# atarimovie.net
KiCad netlist of a schematic drawn in EAGLE
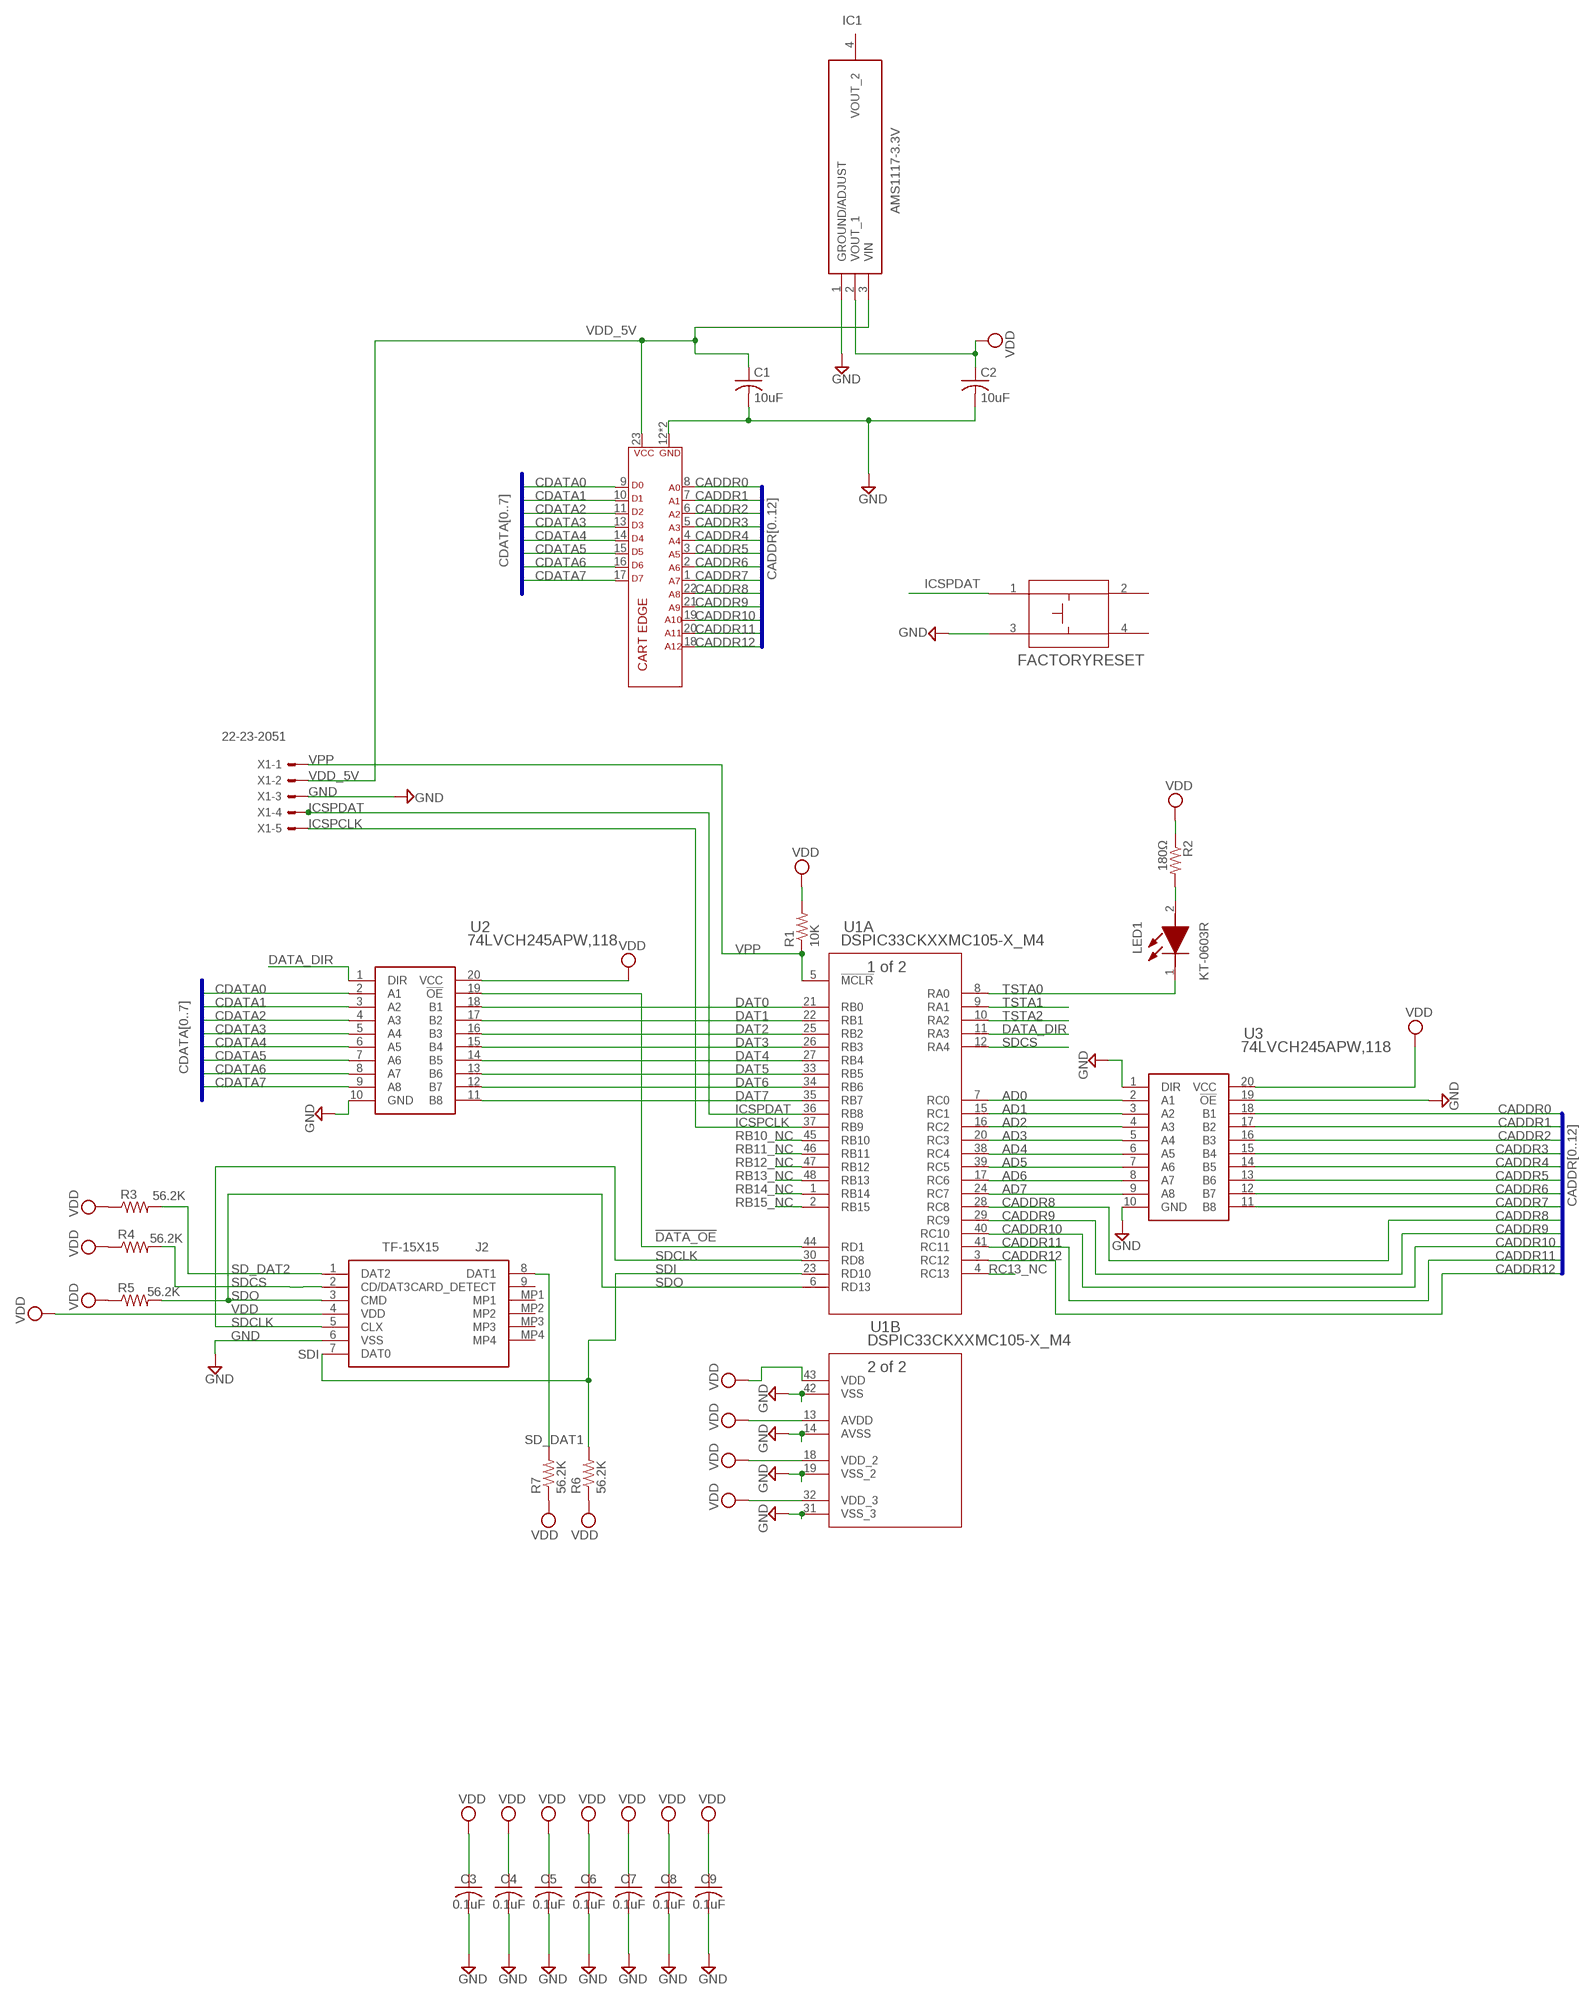
[diagram p0: schematic, sheet 1]

(export (version "E")
  (design (tool "Eeschema 10.0.6"))
  (components
    (comp (ref "C1")
      (value "10uF")
      (footprint "eagle-import:C0603K")
      (libsource (lib "eagle-import") (part "C-USC0603K"))
    )
    (comp (ref "C2")
      (value "10uF")
      (footprint "eagle-import:C0603K")
      (libsource (lib "eagle-import") (part "C-USC0603K"))
    )
    (comp (ref "C3")
      (value "0.1uF")
      (footprint "eagle-import:C0603K")
      (libsource (lib "eagle-import") (part "C-USC0603K"))
    )
    (comp (ref "C4")
      (value "0.1uF")
      (footprint "eagle-import:C0603K")
      (libsource (lib "eagle-import") (part "C-USC0603K"))
    )
    (comp (ref "C5")
      (value "0.1uF")
      (footprint "eagle-import:C0603K")
      (libsource (lib "eagle-import") (part "C-USC0603K"))
    )
    (comp (ref "C6")
      (value "0.1uF")
      (footprint "eagle-import:C0603K")
      (libsource (lib "eagle-import") (part "C-USC0603K"))
    )
    (comp (ref "C7")
      (value "0.1uF")
      (footprint "eagle-import:C0603K")
      (libsource (lib "eagle-import") (part "C-USC0603K"))
    )
    (comp (ref "C8")
      (value "0.1uF")
      (footprint "eagle-import:C0603K")
      (libsource (lib "eagle-import") (part "C-USC0603K"))
    )
    (comp (ref "C9")
      (value "0.1uF")
      (footprint "eagle-import:C0603K")
      (libsource (lib "eagle-import") (part "C-USC0603K"))
    )
    (comp (ref "FACTORYRESET")
      (value "RT3301AF260Q")
      (footprint "eagle-import:RT3301_EWI")
      (fields (field (name "COPYRIGHT") "Copyright (C) 2025 Ultra Librarian. All rights reserved."))
      (libsource (lib "eagle-import") (part "RT3301AF260Q"))
    )
    (comp (ref "IC1")
      (value "AMS1117-3.3V")
      (footprint "eagle-import:SOT229P700X180-4N")
      (fields (field (name "MANUFACTURER_PART_NUMBER") "ams1117-3.3v"))
      (libsource (lib "eagle-import") (part "AMS1117-3.3V"))
    )
    (comp (ref "J1")
      (value "CARTRIDGE EDGE")
      (footprint "eagle-import:MED_TABS_SDACCESS")
      (libsource (lib "eagle-import") (part "ATARI-2600MED_TABS_SDACCESS"))
    )
    (comp (ref "J2")
      (value "TF-15X15")
      (footprint "eagle-import:TF15X15")
      (libsource (lib "eagle-import") (part "TF-15X15"))
    )
    (comp (ref "LED1")
      (value "KT-0603R")
      (footprint "eagle-import:LEDC1608X70N")
      (libsource (lib "eagle-import") (part "KT-0603R"))
    )
    (comp (ref "R1")
      (value "10K")
      (footprint "eagle-import:R0603")
      (libsource (lib "eagle-import") (part "R-US_R0603"))
    )
    (comp (ref "R2")
      (value "180Ω")
      (footprint "eagle-import:R0603")
      (libsource (lib "eagle-import") (part "R-US_R0603"))
    )
    (comp (ref "R3")
      (value "56.2K")
      (footprint "eagle-import:R0603")
      (libsource (lib "eagle-import") (part "R-US_R0603"))
    )
    (comp (ref "R4")
      (value "56.2K")
      (footprint "eagle-import:R0603")
      (libsource (lib "eagle-import") (part "R-US_R0603"))
    )
    (comp (ref "R5")
      (value "56.2K")
      (footprint "eagle-import:R0603")
      (libsource (lib "eagle-import") (part "R-US_R0603"))
    )
    (comp (ref "R6")
      (value "56.2K")
      (footprint "eagle-import:R0603")
      (libsource (lib "eagle-import") (part "R-US_R0603"))
    )
    (comp (ref "R7")
      (value "56.2K")
      (footprint "eagle-import:R0603")
      (libsource (lib "eagle-import") (part "R-US_R0603"))
    )
    (comp (ref "U1")
      (value "DSPIC33CKXXMC105-X_M4")
      (footprint "eagle-import:UQFN48_6X6MC_MCH")
      (fields
        (field (name "MANUFACTURER_PART_NUMBER") "dsPIC33CKXXMC105-X_M4")
        (field (name "COPYRIGHT") "Copyright (C) 2022 Ultra Librarian. All rights reserved.")
      )
      (libsource (lib "eagle-import") (part "DSPIC33CKXXMC105-X_M4"))
    )
    (comp (ref "U2")
      (value "74LVCH245APW,118")
      (footprint "eagle-import:SOP65P640X110-20N")
      (fields (field (name "MOUSER_PART_NUMBER") "771-74LVCH245APW-T"))
      (libsource (lib "eagle-import") (part "74LVCH245APW,118"))
    )
    (comp (ref "U3")
      (value "74LVCH245APW,118")
      (footprint "eagle-import:SOP65P640X110-20N")
      (fields (field (name "MOUSER_PART_NUMBER") "771-74LVCH245APW-T"))
      (libsource (lib "eagle-import") (part "74LVCH245APW,118"))
    )
    (comp (ref "X1")
      (value "22-23-2051")
      (footprint "eagle-import:22-23-2051")
      (fields (field (name "MF") "MOLEX"))
      (libsource (lib "eagle-import") (part "22-23-2051"))
    )
  )
  (nets
    (net (code "1") (name "/AD0") (class "Default")
      (node (ref "U1") (pin "7") (pinfunction "RC0_7") (pintype "bidirectional"))
      (node (ref "U3") (pin "2") (pinfunction "A1_2") (pintype "bidirectional"))
    )
    (net (code "2") (name "/AD1") (class "Default")
      (node (ref "U1") (pin "15") (pinfunction "RC1_15") (pintype "bidirectional"))
      (node (ref "U3") (pin "3") (pinfunction "A2_3") (pintype "bidirectional"))
    )
    (net (code "3") (name "/AD2") (class "Default")
      (node (ref "U1") (pin "16") (pinfunction "RC2_16") (pintype "bidirectional"))
      (node (ref "U3") (pin "4") (pinfunction "A3_4") (pintype "bidirectional"))
    )
    (net (code "4") (name "/AD3") (class "Default")
      (node (ref "U1") (pin "20") (pinfunction "RC3_20") (pintype "bidirectional"))
      (node (ref "U3") (pin "5") (pinfunction "A4_5") (pintype "bidirectional"))
    )
    (net (code "5") (name "/AD4") (class "Default")
      (node (ref "U1") (pin "38") (pinfunction "RC4_38") (pintype "bidirectional"))
      (node (ref "U3") (pin "6") (pinfunction "A5_6") (pintype "bidirectional"))
    )
    (net (code "6") (name "/AD5") (class "Default")
      (node (ref "U1") (pin "39") (pinfunction "RC5_39") (pintype "bidirectional"))
      (node (ref "U3") (pin "7") (pinfunction "A6_7") (pintype "bidirectional"))
    )
    (net (code "7") (name "/AD6") (class "Default")
      (node (ref "U1") (pin "17") (pinfunction "RC6_17") (pintype "bidirectional"))
      (node (ref "U3") (pin "8") (pinfunction "A7_8") (pintype "bidirectional"))
    )
    (net (code "8") (name "/AD7") (class "Default")
      (node (ref "U1") (pin "24") (pinfunction "RC7_24") (pintype "bidirectional"))
      (node (ref "U3") (pin "9") (pinfunction "A8_9") (pintype "bidirectional"))
    )
    (net (code "9") (name "/CADDR0") (class "Default")
      (node (ref "J1") (pin "8") (pinfunction "A0_8") (pintype "bidirectional"))
      (node (ref "U3") (pin "18") (pinfunction "B1_18") (pintype "bidirectional"))
    )
    (net (code "10") (name "/CADDR1") (class "Default")
      (node (ref "J1") (pin "7") (pinfunction "A1_7") (pintype "bidirectional"))
      (node (ref "U3") (pin "17") (pinfunction "B2_17") (pintype "bidirectional"))
    )
    (net (code "11") (name "/CADDR2") (class "Default")
      (node (ref "J1") (pin "6") (pinfunction "A2_6") (pintype "bidirectional"))
      (node (ref "U3") (pin "16") (pinfunction "B3_16") (pintype "bidirectional"))
    )
    (net (code "12") (name "/CADDR3") (class "Default")
      (node (ref "J1") (pin "5") (pinfunction "A3_5") (pintype "bidirectional"))
      (node (ref "U3") (pin "15") (pinfunction "B4_15") (pintype "bidirectional"))
    )
    (net (code "13") (name "/CADDR4") (class "Default")
      (node (ref "J1") (pin "4") (pinfunction "A4_4") (pintype "bidirectional"))
      (node (ref "U3") (pin "14") (pinfunction "B5_14") (pintype "bidirectional"))
    )
    (net (code "14") (name "/CADDR5") (class "Default")
      (node (ref "J1") (pin "3") (pinfunction "A5_3") (pintype "bidirectional"))
      (node (ref "U3") (pin "13") (pinfunction "B6_13") (pintype "bidirectional"))
    )
    (net (code "15") (name "/CADDR6") (class "Default")
      (node (ref "J1") (pin "2") (pinfunction "A6_2") (pintype "bidirectional"))
      (node (ref "U3") (pin "12") (pinfunction "B7_12") (pintype "bidirectional"))
    )
    (net (code "16") (name "/CADDR7") (class "Default")
      (node (ref "J1") (pin "1") (pinfunction "A7_1") (pintype "bidirectional"))
      (node (ref "U3") (pin "11") (pinfunction "B8_11") (pintype "bidirectional"))
    )
    (net (code "17") (name "/CADDR8") (class "Default")
      (node (ref "J1") (pin "22") (pinfunction "A8_22") (pintype "bidirectional"))
      (node (ref "U1") (pin "28") (pinfunction "RC8_28") (pintype "bidirectional"))
    )
    (net (code "18") (name "/CADDR9") (class "Default")
      (node (ref "J1") (pin "21") (pinfunction "A9_21") (pintype "bidirectional"))
      (node (ref "U1") (pin "29") (pinfunction "RC9_29") (pintype "bidirectional"))
    )
    (net (code "19") (name "/CADDR10") (class "Default")
      (node (ref "J1") (pin "19") (pinfunction "A10_19") (pintype "bidirectional"))
      (node (ref "U1") (pin "40") (pinfunction "RC10_40") (pintype "bidirectional"))
    )
    (net (code "20") (name "/CADDR11") (class "Default")
      (node (ref "J1") (pin "20") (pinfunction "A11_20") (pintype "bidirectional"))
      (node (ref "U1") (pin "41") (pinfunction "RC11_41") (pintype "bidirectional"))
    )
    (net (code "21") (name "/CADDR12") (class "Default")
      (node (ref "J1") (pin "18") (pinfunction "A12_18") (pintype "bidirectional"))
      (node (ref "U1") (pin "3") (pinfunction "RC12_3") (pintype "bidirectional"))
    )
    (net (code "23") (name "/CDATA0") (class "Default")
      (node (ref "J1") (pin "9") (pinfunction "D0_9") (pintype "bidirectional"))
      (node (ref "U2") (pin "2") (pinfunction "A1_2") (pintype "bidirectional"))
    )
    (net (code "24") (name "/CDATA1") (class "Default")
      (node (ref "J1") (pin "10") (pinfunction "D1_10") (pintype "bidirectional"))
      (node (ref "U2") (pin "3") (pinfunction "A2_3") (pintype "bidirectional"))
    )
    (net (code "25") (name "/CDATA2") (class "Default")
      (node (ref "J1") (pin "11") (pinfunction "D2_11") (pintype "bidirectional"))
      (node (ref "U2") (pin "4") (pinfunction "A3_4") (pintype "bidirectional"))
    )
    (net (code "26") (name "/CDATA3") (class "Default")
      (node (ref "J1") (pin "13") (pinfunction "D3_13") (pintype "bidirectional"))
      (node (ref "U2") (pin "5") (pinfunction "A4_5") (pintype "bidirectional"))
    )
    (net (code "27") (name "/CDATA4") (class "Default")
      (node (ref "J1") (pin "14") (pinfunction "D4_14") (pintype "bidirectional"))
      (node (ref "U2") (pin "6") (pinfunction "A5_6") (pintype "bidirectional"))
    )
    (net (code "28") (name "/CDATA5") (class "Default")
      (node (ref "J1") (pin "15") (pinfunction "D5_15") (pintype "bidirectional"))
      (node (ref "U2") (pin "7") (pinfunction "A6_7") (pintype "bidirectional"))
    )
    (net (code "29") (name "/CDATA6") (class "Default")
      (node (ref "J1") (pin "16") (pinfunction "D6_16") (pintype "bidirectional"))
      (node (ref "U2") (pin "8") (pinfunction "A7_8") (pintype "bidirectional"))
    )
    (net (code "30") (name "/CDATA7") (class "Default")
      (node (ref "J1") (pin "17") (pinfunction "D7_17") (pintype "bidirectional"))
      (node (ref "U2") (pin "9") (pinfunction "A8_9") (pintype "bidirectional"))
    )
    (net (code "32") (name "/DAT0") (class "Default")
      (node (ref "U1") (pin "21") (pinfunction "RB0_21") (pintype "bidirectional"))
      (node (ref "U2") (pin "18") (pinfunction "B1_18") (pintype "bidirectional"))
    )
    (net (code "33") (name "/DAT1") (class "Default")
      (node (ref "U1") (pin "22") (pinfunction "RB1_22") (pintype "bidirectional"))
      (node (ref "U2") (pin "17") (pinfunction "B2_17") (pintype "bidirectional"))
    )
    (net (code "34") (name "/DAT2") (class "Default")
      (node (ref "U1") (pin "25") (pinfunction "RB2_25") (pintype "bidirectional"))
      (node (ref "U2") (pin "16") (pinfunction "B3_16") (pintype "bidirectional"))
    )
    (net (code "35") (name "/DAT3") (class "Default")
      (node (ref "U1") (pin "26") (pinfunction "RB3_26") (pintype "bidirectional"))
      (node (ref "U2") (pin "15") (pinfunction "B4_15") (pintype "bidirectional"))
    )
    (net (code "36") (name "/DAT4") (class "Default")
      (node (ref "U1") (pin "27") (pinfunction "RB4_27") (pintype "bidirectional"))
      (node (ref "U2") (pin "14") (pinfunction "B5_14") (pintype "bidirectional"))
    )
    (net (code "37") (name "/DAT5") (class "Default")
      (node (ref "U1") (pin "33") (pinfunction "RB5_33") (pintype "bidirectional"))
      (node (ref "U2") (pin "13") (pinfunction "B6_13") (pintype "bidirectional"))
    )
    (net (code "38") (name "/DAT6") (class "Default")
      (node (ref "U1") (pin "34") (pinfunction "RB6_34") (pintype "bidirectional"))
      (node (ref "U2") (pin "12") (pinfunction "B7_12") (pintype "bidirectional"))
    )
    (net (code "39") (name "/DAT7") (class "Default")
      (node (ref "U1") (pin "35") (pinfunction "RB7_35") (pintype "bidirectional"))
      (node (ref "U2") (pin "11") (pinfunction "B8_11") (pintype "bidirectional"))
    )
    (net (code "40") (name "/DATA_DIR") (class "Default")
      (node (ref "U1") (pin "11") (pinfunction "RA3_11") (pintype "bidirectional"))
      (node (ref "U2") (pin "1") (pinfunction "DIR_1") (pintype "bidirectional"))
    )
    (net (code "41") (name "/ICSPCLK") (class "Default")
      (node (ref "U1") (pin "37") (pinfunction "RB9_37") (pintype "bidirectional"))
      (node (ref "X1") (pin "5") (pinfunction "S_5") (pintype "passive"))
    )
    (net (code "42") (name "/ICSPDAT") (class "Default")
      (node (ref "FACTORYRESET") (pin "1") (pinfunction "1_1") (pintype "passive"))
      (node (ref "U1") (pin "36") (pinfunction "RB8_36") (pintype "bidirectional"))
      (node (ref "X1") (pin "4") (pinfunction "S_4") (pintype "passive"))
    )
    (net (code "43") (name "/RB10_NC") (class "Default")
      (node (ref "U1") (pin "45") (pinfunction "RB10_45") (pintype "bidirectional"))
    )
    (net (code "44") (name "/RB11_NC") (class "Default")
      (node (ref "U1") (pin "46") (pinfunction "RB11_46") (pintype "bidirectional"))
    )
    (net (code "45") (name "/RB12_NC") (class "Default")
      (node (ref "U1") (pin "47") (pinfunction "RB12_47") (pintype "bidirectional"))
    )
    (net (code "46") (name "/RB13_NC") (class "Default")
      (node (ref "U1") (pin "48") (pinfunction "RB13_48") (pintype "bidirectional"))
    )
    (net (code "47") (name "/RB14_NC") (class "Default")
      (node (ref "U1") (pin "1") (pinfunction "RB14_1") (pintype "bidirectional"))
    )
    (net (code "48") (name "/RB15_NC") (class "Default")
      (node (ref "U1") (pin "2") (pinfunction "RB15_2") (pintype "bidirectional"))
    )
    (net (code "49") (name "/RC13_NC") (class "Default")
      (node (ref "U1") (pin "4") (pinfunction "RC13_4") (pintype "bidirectional"))
    )
    (net (code "50") (name "/SDCLK") (class "Default")
      (node (ref "J2") (pin "5") (pinfunction "CLX_5") (pintype "bidirectional"))
      (node (ref "U1") (pin "30") (pinfunction "RD8_30") (pintype "bidirectional"))
    )
    (net (code "51") (name "/SDCS") (class "Default")
      (node (ref "J2") (pin "2") (pinfunction "CD/DAT3_2") (pintype "bidirectional"))
      (node (ref "R4") (pin "2") (pinfunction "2_2") (pintype "passive"))
      (node (ref "U1") (pin "12") (pinfunction "RA4_12") (pintype "bidirectional"))
    )
    (net (code "52") (name "/SDI") (class "Default")
      (node (ref "J2") (pin "7") (pinfunction "DAT0_7") (pintype "bidirectional"))
      (node (ref "R6") (pin "2") (pinfunction "2_2") (pintype "passive"))
      (node (ref "U1") (pin "23") (pinfunction "RD10_23") (pintype "bidirectional"))
    )
    (net (code "53") (name "/SDO") (class "Default")
      (node (ref "J2") (pin "3") (pinfunction "CMD_3") (pintype "bidirectional"))
      (node (ref "R5") (pin "2") (pinfunction "2_2") (pintype "passive"))
      (node (ref "U1") (pin "6") (pinfunction "RD13_6") (pintype "bidirectional"))
    )
    (net (code "54") (name "/SD_DAT1") (class "Default")
      (node (ref "J2") (pin "8") (pinfunction "DAT1_8") (pintype "bidirectional"))
      (node (ref "R7") (pin "2") (pinfunction "2_2") (pintype "passive"))
    )
    (net (code "55") (name "/SD_DAT2") (class "Default")
      (node (ref "J2") (pin "1") (pinfunction "DAT2_1") (pintype "bidirectional"))
      (node (ref "R3") (pin "2") (pinfunction "2_2") (pintype "passive"))
    )
    (net (code "56") (name "/TSTA0") (class "Default")
      (node (ref "LED1") (pin "1") (pinfunction "K_1") (pintype "bidirectional"))
      (node (ref "U1") (pin "8") (pinfunction "RA0_8") (pintype "bidirectional"))
    )
    (net (code "57") (name "/TSTA1") (class "Default")
      (node (ref "U1") (pin "9") (pinfunction "RA1_9") (pintype "bidirectional"))
    )
    (net (code "58") (name "/TSTA2") (class "Default")
      (node (ref "U1") (pin "10") (pinfunction "RA2_10") (pintype "bidirectional"))
    )
    (net (code "59") (name "/VDD_5V") (class "Default")
      (node (ref "C1") (pin "1") (pinfunction "1_1") (pintype "passive"))
      (node (ref "IC1") (pin "3") (pinfunction "VIN_3") (pintype "bidirectional"))
      (node (ref "J1") (pin "23") (pinfunction "VCC_23") (pintype "power_in"))
      (node (ref "X1") (pin "2") (pinfunction "S_2") (pintype "passive"))
    )
    (net (code "60") (name "/VPP") (class "Default")
      (node (ref "R1") (pin "1") (pinfunction "1_1") (pintype "passive"))
      (node (ref "U1") (pin "5") (pinfunction "~{MCLR}_5") (pintype "input"))
      (node (ref "X1") (pin "1") (pinfunction "S_1") (pintype "passive"))
    )
    (net (code "61") (name "/~{DATA_OE}") (class "Default")
      (node (ref "U1") (pin "44") (pinfunction "RD1_44") (pintype "bidirectional"))
      (node (ref "U2") (pin "19") (pinfunction "~{OE}_19") (pintype "bidirectional"))
    )
    (net (code "62") (name "GND") (class "Default")
      (node (ref "C1") (pin "2") (pinfunction "2_2") (pintype "passive"))
      (node (ref "C2") (pin "2") (pinfunction "2_2") (pintype "passive"))
      (node (ref "C3") (pin "2") (pinfunction "2_2") (pintype "passive"))
      (node (ref "C4") (pin "2") (pinfunction "2_2") (pintype "passive"))
      (node (ref "C5") (pin "2") (pinfunction "2_2") (pintype "passive"))
      (node (ref "C6") (pin "2") (pinfunction "2_2") (pintype "passive"))
      (node (ref "C7") (pin "2") (pinfunction "2_2") (pintype "passive"))
      (node (ref "C8") (pin "2") (pinfunction "2_2") (pintype "passive"))
      (node (ref "C9") (pin "2") (pinfunction "2_2") (pintype "passive"))
      (node (ref "FACTORYRESET") (pin "3") (pinfunction "3_3") (pintype "passive"))
      (node (ref "IC1") (pin "1") (pinfunction "GROUND/ADJUST_1") (pintype "bidirectional"))
      (node (ref "J1") (pin "12") (pinfunction "GND_12") (pintype "power_in"))
      (node (ref "J1") (pin "24") (pinfunction "GND_24") (pintype "power_in"))
      (node (ref "J2") (pin "6") (pinfunction "VSS_6") (pintype "bidirectional"))
      (node (ref "U1") (pin "14") (pinfunction "AVSS_14") (pintype "power_in"))
      (node (ref "U1") (pin "19") (pinfunction "VSS_2_19") (pintype "power_in"))
      (node (ref "U1") (pin "31") (pinfunction "VSS_3_31") (pintype "power_in"))
      (node (ref "U1") (pin "42") (pinfunction "VSS_42") (pintype "power_in"))
      (node (ref "U2") (pin "10") (pinfunction "GND_10") (pintype "bidirectional"))
      (node (ref "U3") (pin "1") (pinfunction "DIR_1") (pintype "bidirectional"))
      (node (ref "U3") (pin "10") (pinfunction "GND_10") (pintype "bidirectional"))
      (node (ref "U3") (pin "19") (pinfunction "~{OE}_19") (pintype "bidirectional"))
      (node (ref "X1") (pin "3") (pinfunction "S_3") (pintype "passive"))
    )
    (net (code "63") (name "Net-(LED1-A)") (class "Default")
      (node (ref "LED1") (pin "2") (pinfunction "A_2") (pintype "bidirectional"))
      (node (ref "R2") (pin "2") (pinfunction "2_2") (pintype "passive"))
    )
    (net (code "64") (name "VDD") (class "Default")
      (node (ref "C2") (pin "1") (pinfunction "1_1") (pintype "passive"))
      (node (ref "C3") (pin "1") (pinfunction "1_1") (pintype "passive"))
      (node (ref "C4") (pin "1") (pinfunction "1_1") (pintype "passive"))
      (node (ref "C5") (pin "1") (pinfunction "1_1") (pintype "passive"))
      (node (ref "C6") (pin "1") (pinfunction "1_1") (pintype "passive"))
      (node (ref "C7") (pin "1") (pinfunction "1_1") (pintype "passive"))
      (node (ref "C8") (pin "1") (pinfunction "1_1") (pintype "passive"))
      (node (ref "C9") (pin "1") (pinfunction "1_1") (pintype "passive"))
      (node (ref "IC1") (pin "2") (pinfunction "VOUT_1_2") (pintype "bidirectional"))
      (node (ref "J2") (pin "4") (pinfunction "VDD_4") (pintype "bidirectional"))
      (node (ref "R1") (pin "2") (pinfunction "2_2") (pintype "passive"))
      (node (ref "R2") (pin "1") (pinfunction "1_1") (pintype "passive"))
      (node (ref "R3") (pin "1") (pinfunction "1_1") (pintype "passive"))
      (node (ref "R4") (pin "1") (pinfunction "1_1") (pintype "passive"))
      (node (ref "R5") (pin "1") (pinfunction "1_1") (pintype "passive"))
      (node (ref "R6") (pin "1") (pinfunction "1_1") (pintype "passive"))
      (node (ref "R7") (pin "1") (pinfunction "1_1") (pintype "passive"))
      (node (ref "U1") (pin "13") (pinfunction "AVDD_13") (pintype "power_in"))
      (node (ref "U1") (pin "18") (pinfunction "VDD_2_18") (pintype "power_in"))
      (node (ref "U1") (pin "32") (pinfunction "VDD_3_32") (pintype "power_in"))
      (node (ref "U1") (pin "43") (pinfunction "VDD_43") (pintype "power_in"))
      (node (ref "U2") (pin "20") (pinfunction "VCC_20") (pintype "bidirectional"))
      (node (ref "U3") (pin "20") (pinfunction "VCC_20") (pintype "bidirectional"))
    )
    (net (code "65") (name "unconnected-(FACTORYRESET-Pad2)") (class "Default")
      (node (ref "FACTORYRESET") (pin "2") (pinfunction "2_2") (pintype "passive"))
    )
    (net (code "66") (name "unconnected-(FACTORYRESET-Pad4)") (class "Default")
      (node (ref "FACTORYRESET") (pin "4") (pinfunction "4_4") (pintype "passive"))
    )
    (net (code "67") (name "unconnected-(IC1-VOUT_2-Pad4)") (class "Default")
      (node (ref "IC1") (pin "4") (pinfunction "VOUT_2_4") (pintype "bidirectional"))
    )
    (net (code "68") (name "unconnected-(J2-CARD_DETECT-Pad9)") (class "Default")
      (node (ref "J2") (pin "9") (pinfunction "CARD_DETECT_9") (pintype "bidirectional"))
    )
    (net (code "69") (name "unconnected-(J2-PadMP1)") (class "Default")
      (node (ref "J2") (pin "MP1") (pinfunction "MP1_MP1") (pintype "bidirectional"))
    )
    (net (code "70") (name "unconnected-(J2-PadMP2)") (class "Default")
      (node (ref "J2") (pin "MP2") (pinfunction "MP2_MP2") (pintype "bidirectional"))
    )
    (net (code "71") (name "unconnected-(J2-PadMP3)") (class "Default")
      (node (ref "J2") (pin "MP3") (pinfunction "MP3_MP3") (pintype "bidirectional"))
    )
    (net (code "72") (name "unconnected-(J2-PadMP4)") (class "Default")
      (node (ref "J2") (pin "MP4") (pinfunction "MP4_MP4") (pintype "bidirectional"))
    )
  )
)
